# 15-15_AC_DC_Dual_power_supply.net
KiCad netlist of a schematic drawn in EAGLE
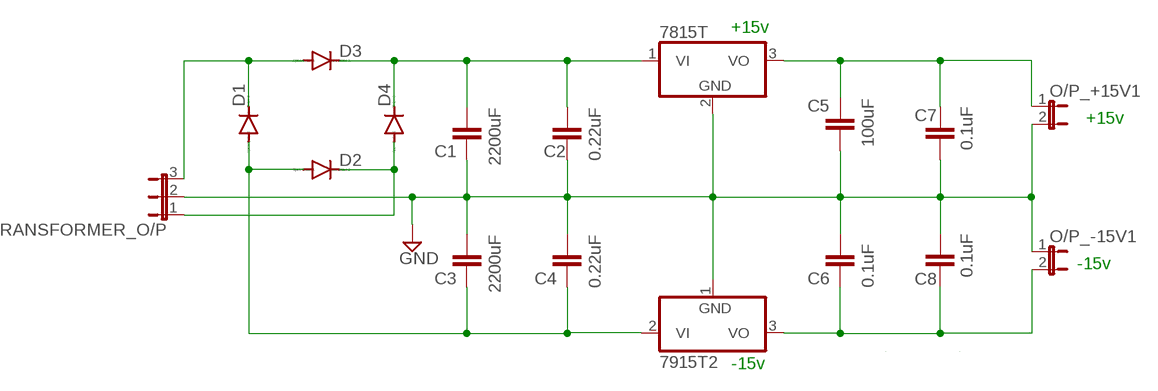
[diagram p0: schematic, sheet 1]

(export (version "E")
  (design (tool "Eeschema 10.0.6"))
  (components
    (comp (ref "+15V2")
      (value "7815T")
      (footprint "eagle-import:TO220H")
      (libsource (lib "eagle-import") (part "78T15"))
    )
    (comp (ref "7915T2")
      (value "7915T")
      (footprint "eagle-import:TO220H")
      (libsource (lib "eagle-import") (part "79T15"))
    )
    (comp (ref "C1")
      (value "2200uF")
      (footprint "eagle-import:C2.5-2")
      (libsource (lib "eagle-import") (part "C2.5/2"))
    )
    (comp (ref "C2")
      (value "0.22uF")
      (footprint "eagle-import:C2.5-2")
      (libsource (lib "eagle-import") (part "C2.5/2"))
    )
    (comp (ref "C3")
      (value "2200uF")
      (footprint "eagle-import:C2.5-2")
      (libsource (lib "eagle-import") (part "C2.5/2"))
    )
    (comp (ref "C4")
      (value "0.22uF")
      (footprint "eagle-import:C2.5-2")
      (libsource (lib "eagle-import") (part "C2.5/2"))
    )
    (comp (ref "C5")
      (value "100uF")
      (footprint "eagle-import:C2.5-2")
      (libsource (lib "eagle-import") (part "C2.5/2"))
    )
    (comp (ref "C6")
      (value "0.1uF")
      (footprint "eagle-import:C2.5-2")
      (libsource (lib "eagle-import") (part "C2.5/2"))
    )
    (comp (ref "C7")
      (value "0.1uF")
      (footprint "eagle-import:C2.5-3")
      (libsource (lib "eagle-import") (part "C2,5-3"))
    )
    (comp (ref "C8")
      (value "0.1uF")
      (footprint "eagle-import:C2.5-3")
      (libsource (lib "eagle-import") (part "C2,5-3"))
    )
    (comp (ref "D1")
      (value "1N4004")
      (footprint "eagle-import:DO41-10")
      (libsource (lib "eagle-import") (part "1N4004"))
    )
    (comp (ref "D2")
      (value "1N4004")
      (footprint "eagle-import:DO41-10")
      (libsource (lib "eagle-import") (part "1N4004"))
    )
    (comp (ref "D3")
      (value "1N4004")
      (footprint "eagle-import:DO41-10")
      (libsource (lib "eagle-import") (part "1N4004"))
    )
    (comp (ref "D4")
      (value "1N4004")
      (footprint "eagle-import:DO41-10")
      (libsource (lib "eagle-import") (part "1N4004"))
    )
    (comp (ref "O/P_+15V1")
      (value "JP1E")
      (footprint "eagle-import:JP1")
      (libsource (lib "eagle-import") (part "JP1E"))
    )
    (comp (ref "O/P_-15V1")
      (value "JP1E")
      (footprint "eagle-import:JP1")
      (libsource (lib "eagle-import") (part "JP1E"))
    )
    (comp (ref "TRANSFORMER_O/P")
      (value "JP2E")
      (footprint "eagle-import:JP2")
      (libsource (lib "eagle-import") (part "JP2E"))
    )
  )
  (nets
    (net (code "1") (name "GND") (class "Default")
      (node (ref "+15V2") (pin "2") (pinfunction "GND_2") (pintype "passive"))
      (node (ref "7915T2") (pin "1") (pinfunction "GND_1") (pintype "passive"))
      (node (ref "C1") (pin "1") (pinfunction "1_1") (pintype "passive"))
      (node (ref "C2") (pin "1") (pinfunction "1_1") (pintype "passive"))
      (node (ref "C3") (pin "2") (pinfunction "2_2") (pintype "passive"))
      (node (ref "C4") (pin "2") (pinfunction "2_2") (pintype "passive"))
      (node (ref "C5") (pin "1") (pinfunction "1_1") (pintype "passive"))
      (node (ref "C6") (pin "2") (pinfunction "2_2") (pintype "passive"))
      (node (ref "C7") (pin "2") (pinfunction "2_2") (pintype "passive"))
      (node (ref "C8") (pin "1") (pinfunction "1_1") (pintype "passive"))
      (node (ref "TRANSFORMER_O/P") (pin "2") (pinfunction "2_2") (pintype "passive"))
    )
    (net (code "2") (name "Net-(+15V2-VI)") (class "Default")
      (node (ref "+15V2") (pin "1") (pinfunction "VI_1") (pintype "input"))
      (node (ref "C1") (pin "2") (pinfunction "2_2") (pintype "passive"))
      (node (ref "C2") (pin "2") (pinfunction "2_2") (pintype "passive"))
      (node (ref "D3") (pin "C") (pinfunction "C_C") (pintype "passive"))
      (node (ref "D4") (pin "C") (pinfunction "C_C") (pintype "passive"))
    )
    (net (code "3") (name "Net-(+15V2-VO)") (class "Default")
      (node (ref "+15V2") (pin "3") (pinfunction "VO_3") (pintype "passive"))
      (node (ref "C5") (pin "2") (pinfunction "2_2") (pintype "passive"))
      (node (ref "C7") (pin "1") (pinfunction "1_1") (pintype "passive"))
      (node (ref "O/P_+15V1") (pin "1") (pinfunction "1_1") (pintype "passive"))
    )
    (net (code "4") (name "Net-(7915T2-VI)") (class "Default")
      (node (ref "7915T2") (pin "2") (pinfunction "VI_2") (pintype "input"))
      (node (ref "C3") (pin "1") (pinfunction "1_1") (pintype "passive"))
      (node (ref "C4") (pin "1") (pinfunction "1_1") (pintype "passive"))
      (node (ref "D1") (pin "A") (pinfunction "A_A") (pintype "passive"))
      (node (ref "D2") (pin "A") (pinfunction "A_A") (pintype "passive"))
    )
    (net (code "5") (name "Net-(7915T2-VO)") (class "Default")
      (node (ref "7915T2") (pin "3") (pinfunction "VO_3") (pintype "passive"))
      (node (ref "C6") (pin "1") (pinfunction "1_1") (pintype "passive"))
    )
    (net (code "6") (name "Net-(C8-Pad2)") (class "Default")
      (node (ref "C8") (pin "2") (pinfunction "2_2") (pintype "passive"))
      (node (ref "O/P_-15V1") (pin "2") (pinfunction "2_2") (pintype "passive"))
    )
    (net (code "7") (name "Net-(D1-PadC)") (class "Default")
      (node (ref "D1") (pin "C") (pinfunction "C_C") (pintype "passive"))
      (node (ref "D3") (pin "A") (pinfunction "A_A") (pintype "passive"))
      (node (ref "TRANSFORMER_O/P") (pin "3") (pinfunction "3_3") (pintype "passive"))
    )
    (net (code "8") (name "Net-(D2-PadC)") (class "Default")
      (node (ref "D2") (pin "C") (pinfunction "C_C") (pintype "passive"))
      (node (ref "D4") (pin "A") (pinfunction "A_A") (pintype "passive"))
      (node (ref "TRANSFORMER_O/P") (pin "1") (pinfunction "1_1") (pintype "passive"))
    )
    (net (code "9") (name "Net-(O/P_+15V1-Pad2)") (class "Default")
      (node (ref "O/P_+15V1") (pin "2") (pinfunction "2_2") (pintype "passive"))
      (node (ref "O/P_-15V1") (pin "1") (pinfunction "1_1") (pintype "passive"))
    )
  )
)
